# MAX485.net
KiCad netlist of a schematic drawn in Altium Designer
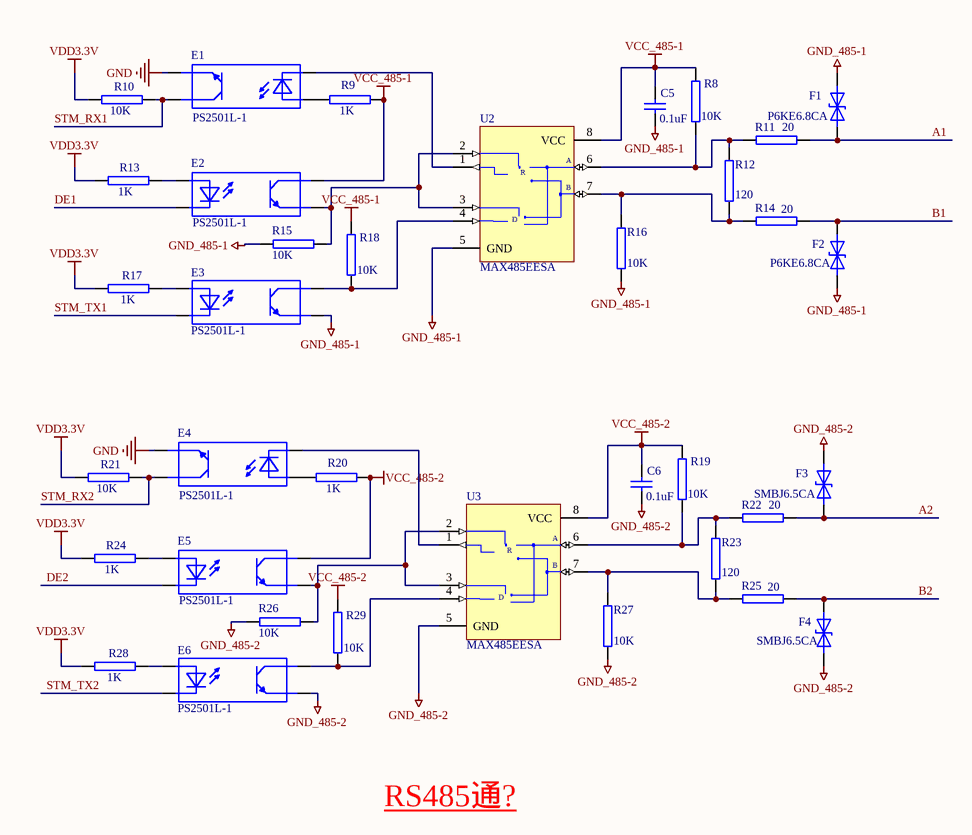
[diagram p0: MAX485.SchDoc]

(export (version "E")
  (design (tool "Eeschema 10.0.6"))
  (components
    (comp (ref "C5")
      (value "0.1uF")
      (footprint "C0805")
      (description "Capacitor")
      (fields (field (name "Comment") "Cap") (field (name "PUBLISHER") "Altium Limited"))
      (libsource (lib "destiny") (part "Cap"))
    )
    (comp (ref "C6")
      (value "0.1uF")
      (footprint "C0805")
      (description "Capacitor")
      (fields (field (name "Comment") "Cap") (field (name "PUBLISHER") "Altium Limited"))
      (libsource (lib "destiny") (part "Cap"))
    )
    (comp (ref "E1") (value "PS2501L-1") (description "光耦") (libsource (lib "*") (part "OPTO1")))
    (comp (ref "E2") (value "PS2501L-1") (description "光耦") (libsource (lib "*") (part "OPTO1")))
    (comp (ref "E3") (value "PS2501L-1") (description "光耦") (libsource (lib "*") (part "OPTO1")))
    (comp (ref "E4") (value "PS2501L-1") (description "光耦") (libsource (lib "*") (part "OPTO1")))
    (comp (ref "E5") (value "PS2501L-1") (description "光耦") (libsource (lib "*") (part "OPTO1")))
    (comp (ref "E6") (value "PS2501L-1") (description "光耦") (libsource (lib "*") (part "OPTO1")))
    (comp (ref "F1") (value "P6KE6.8CA") (description "快速瞬变二极管") (libsource (lib "*") (part "TVS")))
    (comp (ref "F2") (value "P6KE6.8CA") (description "快速瞬变二极管") (libsource (lib "*") (part "TVS")))
    (comp (ref "F3") (value "SMBJ6.5CA") (description "快速瞬变二极管") (libsource (lib "*") (part "TVS")))
    (comp (ref "F4") (value "SMBJ6.5CA") (description "快速瞬变二极管") (libsource (lib "*") (part "TVS")))
    (comp (ref "R8") (value "10K") (footprint "0805") (libsource (lib "Integrated_Library1") (part "RES2")))
    (comp (ref "R9") (value "1K") (footprint "0805") (libsource (lib "Integrated_Library1") (part "RES2")))
    (comp (ref "R10") (value "10K") (footprint "0805") (libsource (lib "Integrated_Library1") (part "RES2")))
    (comp (ref "R11") (value "20") (footprint "0805") (libsource (lib "Integrated_Library1") (part "RES2")))
    (comp (ref "R12") (value "120") (footprint "0805") (libsource (lib "Integrated_Library1") (part "RES2")))
    (comp (ref "R13") (value "1K") (footprint "0805") (libsource (lib "Integrated_Library1") (part "RES2")))
    (comp (ref "R14") (value "20") (footprint "0805") (libsource (lib "Integrated_Library1") (part "RES2")))
    (comp (ref "R15") (value "10K") (footprint "0805") (libsource (lib "Integrated_Library1") (part "RES2")))
    (comp (ref "R16") (value "10K") (footprint "0805") (libsource (lib "Integrated_Library1") (part "RES2")))
    (comp (ref "R17") (value "1K") (footprint "0805") (libsource (lib "Integrated_Library1") (part "RES2")))
    (comp (ref "R18") (value "10K") (footprint "0805") (libsource (lib "Integrated_Library1") (part "RES2")))
    (comp (ref "R19") (value "10K") (footprint "0805") (libsource (lib "Integrated_Library1") (part "RES2")))
    (comp (ref "R20") (value "1K") (footprint "0805") (libsource (lib "Integrated_Library1") (part "RES2")))
    (comp (ref "R21") (value "10K") (footprint "0805") (libsource (lib "Integrated_Library1") (part "RES2")))
    (comp (ref "R22") (value "20") (footprint "0805") (libsource (lib "Integrated_Library1") (part "RES2")))
    (comp (ref "R23") (value "120") (footprint "0805") (libsource (lib "Integrated_Library1") (part "RES2")))
    (comp (ref "R24") (value "1K") (footprint "0805") (libsource (lib "Integrated_Library1") (part "RES2")))
    (comp (ref "R25") (value "20") (footprint "0805") (libsource (lib "Integrated_Library1") (part "RES2")))
    (comp (ref "R26") (value "10K") (footprint "0805") (libsource (lib "Integrated_Library1") (part "RES2")))
    (comp (ref "R27") (value "10K") (footprint "0805") (libsource (lib "Integrated_Library1") (part "RES2")))
    (comp (ref "R28") (value "1K") (footprint "0805") (libsource (lib "Integrated_Library1") (part "RES2")))
    (comp (ref "R29") (value "10K") (footprint "0805") (libsource (lib "Integrated_Library1") (part "RES2")))
    (comp (ref "U2")
      (value "MAX485EESA")
      (footprint "NSO8")
      (description "Low-Power, Slew-Rate-Limited RS-485/RS-422 Transceiver")
      (fields (field (name "PUBLISHER") "Altium Limited"))
      (libsource (lib "main board") (part "MAX485ESA"))
    )
    (comp (ref "U3")
      (value "MAX485EESA")
      (footprint "NSO8")
      (description "Low-Power, Slew-Rate-Limited RS-485/RS-422 Transceiver")
      (fields (field (name "PUBLISHER") "Altium Limited"))
      (libsource (lib "main board") (part "MAX485ESA"))
    )
  )
  (nets
    (net (code "1") (name "/A1") (class "Default")
      (node (ref "F1") (pin "2") (pintype "passive"))
      (node (ref "R11") (pin "2") (pintype "passive"))
    )
    (net (code "2") (name "/A2") (class "Default")
      (node (ref "F3") (pin "2") (pintype "passive"))
      (node (ref "R22") (pin "2") (pintype "passive"))
    )
    (net (code "3") (name "/B1") (class "Default")
      (node (ref "F2") (pin "1") (pintype "passive"))
      (node (ref "R14") (pin "2") (pintype "passive"))
    )
    (net (code "4") (name "/B2") (class "Default")
      (node (ref "F4") (pin "1") (pintype "passive"))
      (node (ref "R25") (pin "2") (pintype "passive"))
    )
    (net (code "5") (name "/DE1") (class "Default") (node (ref "E2") (pin "2") (pintype "passive")))
    (net (code "6") (name "/DE2") (class "Default") (node (ref "E5") (pin "2") (pintype "passive")))
    (net (code "7") (name "/STM_RX1") (class "Default")
      (node (ref "E1") (pin "4") (pintype "passive"))
      (node (ref "R10") (pin "1") (pintype "passive"))
    )
    (net (code "8") (name "/STM_RX2") (class "Default")
      (node (ref "E4") (pin "4") (pintype "passive"))
      (node (ref "R21") (pin "1") (pintype "passive"))
    )
    (net (code "9") (name "/STM_TX1") (class "Default") (node (ref "E3") (pin "2") (pintype "passive")))
    (net (code "10") (name "/STM_TX2") (class "Default") (node (ref "E6") (pin "2") (pintype "passive")))
    (net (code "11") (name "GND") (class "Default")
      (node (ref "E1") (pin "3") (pintype "passive"))
      (node (ref "E4") (pin "3") (pintype "passive"))
    )
    (net (code "12") (name "GND_485-1") (class "Default")
      (node (ref "C5") (pin "1") (pinfunction "1_1") (pintype "passive"))
      (node (ref "E3") (pin "3") (pintype "passive"))
      (node (ref "F1") (pin "1") (pintype "passive"))
      (node (ref "F2") (pin "2") (pintype "passive"))
      (node (ref "R15") (pin "2") (pintype "passive"))
      (node (ref "R16") (pin "1") (pintype "passive"))
      (node (ref "U2") (pin "5") (pinfunction "GND_5") (pintype "power_in"))
    )
    (net (code "13") (name "GND_485-2") (class "Default")
      (node (ref "C6") (pin "1") (pinfunction "1_1") (pintype "passive"))
      (node (ref "E6") (pin "3") (pintype "passive"))
      (node (ref "F3") (pin "1") (pintype "passive"))
      (node (ref "F4") (pin "2") (pintype "passive"))
      (node (ref "R26") (pin "2") (pintype "passive"))
      (node (ref "R27") (pin "1") (pintype "passive"))
      (node (ref "U3") (pin "5") (pinfunction "GND_5") (pintype "power_in"))
    )
    (net (code "14") (name "Net-(E1-Pad1)") (class "Default")
      (node (ref "E1") (pin "1") (pintype "passive"))
      (node (ref "R9") (pin "2") (pintype "passive"))
    )
    (net (code "15") (name "Net-(E2-Pad1)") (class "Default")
      (node (ref "E2") (pin "1") (pintype "passive"))
      (node (ref "R13") (pin "1") (pintype "passive"))
    )
    (net (code "16") (name "Net-(E3-Pad1)") (class "Default")
      (node (ref "E3") (pin "1") (pintype "passive"))
      (node (ref "R17") (pin "1") (pintype "passive"))
    )
    (net (code "17") (name "Net-(E4-Pad1)") (class "Default")
      (node (ref "E4") (pin "1") (pintype "passive"))
      (node (ref "R20") (pin "2") (pintype "passive"))
    )
    (net (code "18") (name "Net-(E5-Pad1)") (class "Default")
      (node (ref "E5") (pin "1") (pintype "passive"))
      (node (ref "R24") (pin "1") (pintype "passive"))
    )
    (net (code "19") (name "Net-(E6-Pad1)") (class "Default")
      (node (ref "E6") (pin "1") (pintype "passive"))
      (node (ref "R28") (pin "1") (pintype "passive"))
    )
    (net (code "20") (name "Net-(U2-A)") (class "Default")
      (node (ref "R11") (pin "1") (pintype "passive"))
      (node (ref "R12") (pin "2") (pintype "passive"))
      (node (ref "R8") (pin "1") (pintype "passive"))
      (node (ref "U2") (pin "6") (pinfunction "A_6") (pintype "bidirectional"))
    )
    (net (code "21") (name "Net-(U2-B)") (class "Default")
      (node (ref "R12") (pin "1") (pintype "passive"))
      (node (ref "R14") (pin "1") (pintype "passive"))
      (node (ref "R16") (pin "2") (pintype "passive"))
      (node (ref "U2") (pin "7") (pinfunction "B_7") (pintype "bidirectional"))
    )
    (net (code "22") (name "Net-(U2-DE)") (class "Default")
      (node (ref "E2") (pin "3") (pintype "passive"))
      (node (ref "R15") (pin "1") (pintype "passive"))
      (node (ref "U2") (pin "2") (pinfunction "~{RE}_2") (pintype "input"))
      (node (ref "U2") (pin "3") (pinfunction "DE_3") (pintype "input"))
    )
    (net (code "23") (name "Net-(U2-DI)") (class "Default")
      (node (ref "E3") (pin "4") (pintype "passive"))
      (node (ref "R18") (pin "1") (pintype "passive"))
      (node (ref "U2") (pin "4") (pinfunction "DI_4") (pintype "input"))
    )
    (net (code "24") (name "Net-(U2-RO)") (class "Default")
      (node (ref "E1") (pin "2") (pintype "passive"))
      (node (ref "U2") (pin "1") (pinfunction "RO_1") (pintype "output"))
    )
    (net (code "25") (name "Net-(U3-A)") (class "Default")
      (node (ref "R19") (pin "1") (pintype "passive"))
      (node (ref "R22") (pin "1") (pintype "passive"))
      (node (ref "R23") (pin "2") (pintype "passive"))
      (node (ref "U3") (pin "6") (pinfunction "A_6") (pintype "bidirectional"))
    )
    (net (code "26") (name "Net-(U3-B)") (class "Default")
      (node (ref "R23") (pin "1") (pintype "passive"))
      (node (ref "R25") (pin "1") (pintype "passive"))
      (node (ref "R27") (pin "2") (pintype "passive"))
      (node (ref "U3") (pin "7") (pinfunction "B_7") (pintype "bidirectional"))
    )
    (net (code "27") (name "Net-(U3-DE)") (class "Default")
      (node (ref "E5") (pin "3") (pintype "passive"))
      (node (ref "R26") (pin "1") (pintype "passive"))
      (node (ref "U3") (pin "2") (pinfunction "~{RE}_2") (pintype "input"))
      (node (ref "U3") (pin "3") (pinfunction "DE_3") (pintype "input"))
    )
    (net (code "28") (name "Net-(U3-DI)") (class "Default")
      (node (ref "E6") (pin "4") (pintype "passive"))
      (node (ref "R29") (pin "1") (pintype "passive"))
      (node (ref "U3") (pin "4") (pinfunction "DI_4") (pintype "input"))
    )
    (net (code "29") (name "Net-(U3-RO)") (class "Default")
      (node (ref "E4") (pin "2") (pintype "passive"))
      (node (ref "U3") (pin "1") (pinfunction "RO_1") (pintype "output"))
    )
    (net (code "30") (name "VCC_485-1") (class "Default")
      (node (ref "C5") (pin "2") (pinfunction "2_2") (pintype "passive"))
      (node (ref "E2") (pin "4") (pintype "passive"))
      (node (ref "R18") (pin "2") (pintype "passive"))
      (node (ref "R8") (pin "2") (pintype "passive"))
      (node (ref "R9") (pin "1") (pintype "passive"))
      (node (ref "U2") (pin "8") (pinfunction "VCC_8") (pintype "power_in"))
    )
    (net (code "31") (name "VCC_485-2") (class "Default")
      (node (ref "C6") (pin "2") (pinfunction "2_2") (pintype "passive"))
      (node (ref "E5") (pin "4") (pintype "passive"))
      (node (ref "R19") (pin "2") (pintype "passive"))
      (node (ref "R20") (pin "1") (pintype "passive"))
      (node (ref "R29") (pin "2") (pintype "passive"))
      (node (ref "U3") (pin "8") (pinfunction "VCC_8") (pintype "power_in"))
    )
    (net (code "32") (name "VDD3.3V") (class "Default")
      (node (ref "R10") (pin "2") (pintype "passive"))
      (node (ref "R13") (pin "2") (pintype "passive"))
      (node (ref "R17") (pin "2") (pintype "passive"))
      (node (ref "R21") (pin "2") (pintype "passive"))
      (node (ref "R24") (pin "2") (pintype "passive"))
      (node (ref "R28") (pin "2") (pintype "passive"))
    )
  )
)
